# design.net
KiCad netlist of a schematic drawn in Altium Designer
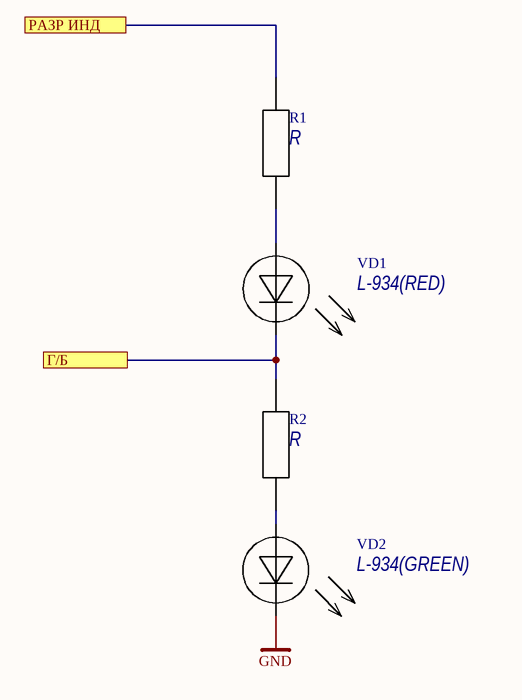
[diagram p0: СВЕТОДИОДЫ.SchDoc]

(export (version "E")
  (design (tool "Eeschema 10.0.6"))
  (components
    (comp (ref "R1") (value "R") (footprint "R") (libsource (lib "UGO") (part "R")))
    (comp (ref "R2") (value "R") (footprint "R") (libsource (lib "UGO") (part "R")))
    (comp (ref "VD1")
      (value "L-934(RED)")
      (footprint "L-934(RED)")
      (libsource (lib "UGO") (part "L-934(RED)"))
    )
    (comp (ref "VD2")
      (value "L-934(GREEN)")
      (footprint "L-934(GREEN)")
      (libsource (lib "UGO") (part "L-934(GREEN)"))
    )
  )
  (nets
    (net (code "1") (name "/Г{slash}Б") (class "Default")
      (node (ref "R2") (pin "2") (pintype "passive"))
      (node (ref "VD1") (pin "2") (pintype "passive"))
    )
    (net (code "2") (name "/РАЗР ИНД") (class "Default") (node (ref "R1") (pin "2") (pintype "passive")))
    (net (code "3") (name "GND") (class "Default") (node (ref "VD2") (pin "2") (pintype "passive")))
    (net (code "4") (name "Net-(R1-Pad1)") (class "Default")
      (node (ref "R1") (pin "1") (pintype "passive"))
      (node (ref "VD1") (pin "1") (pintype "passive"))
    )
    (net (code "5") (name "Net-(R2-Pad1)") (class "Default")
      (node (ref "R2") (pin "1") (pintype "passive"))
      (node (ref "VD2") (pin "1") (pintype "passive"))
    )
  )
)
